# ProPrj_USB_Hub_Port_PCB_2026-06-07.net
KiCad netlist of a schematic drawn in EasyEDA Pro
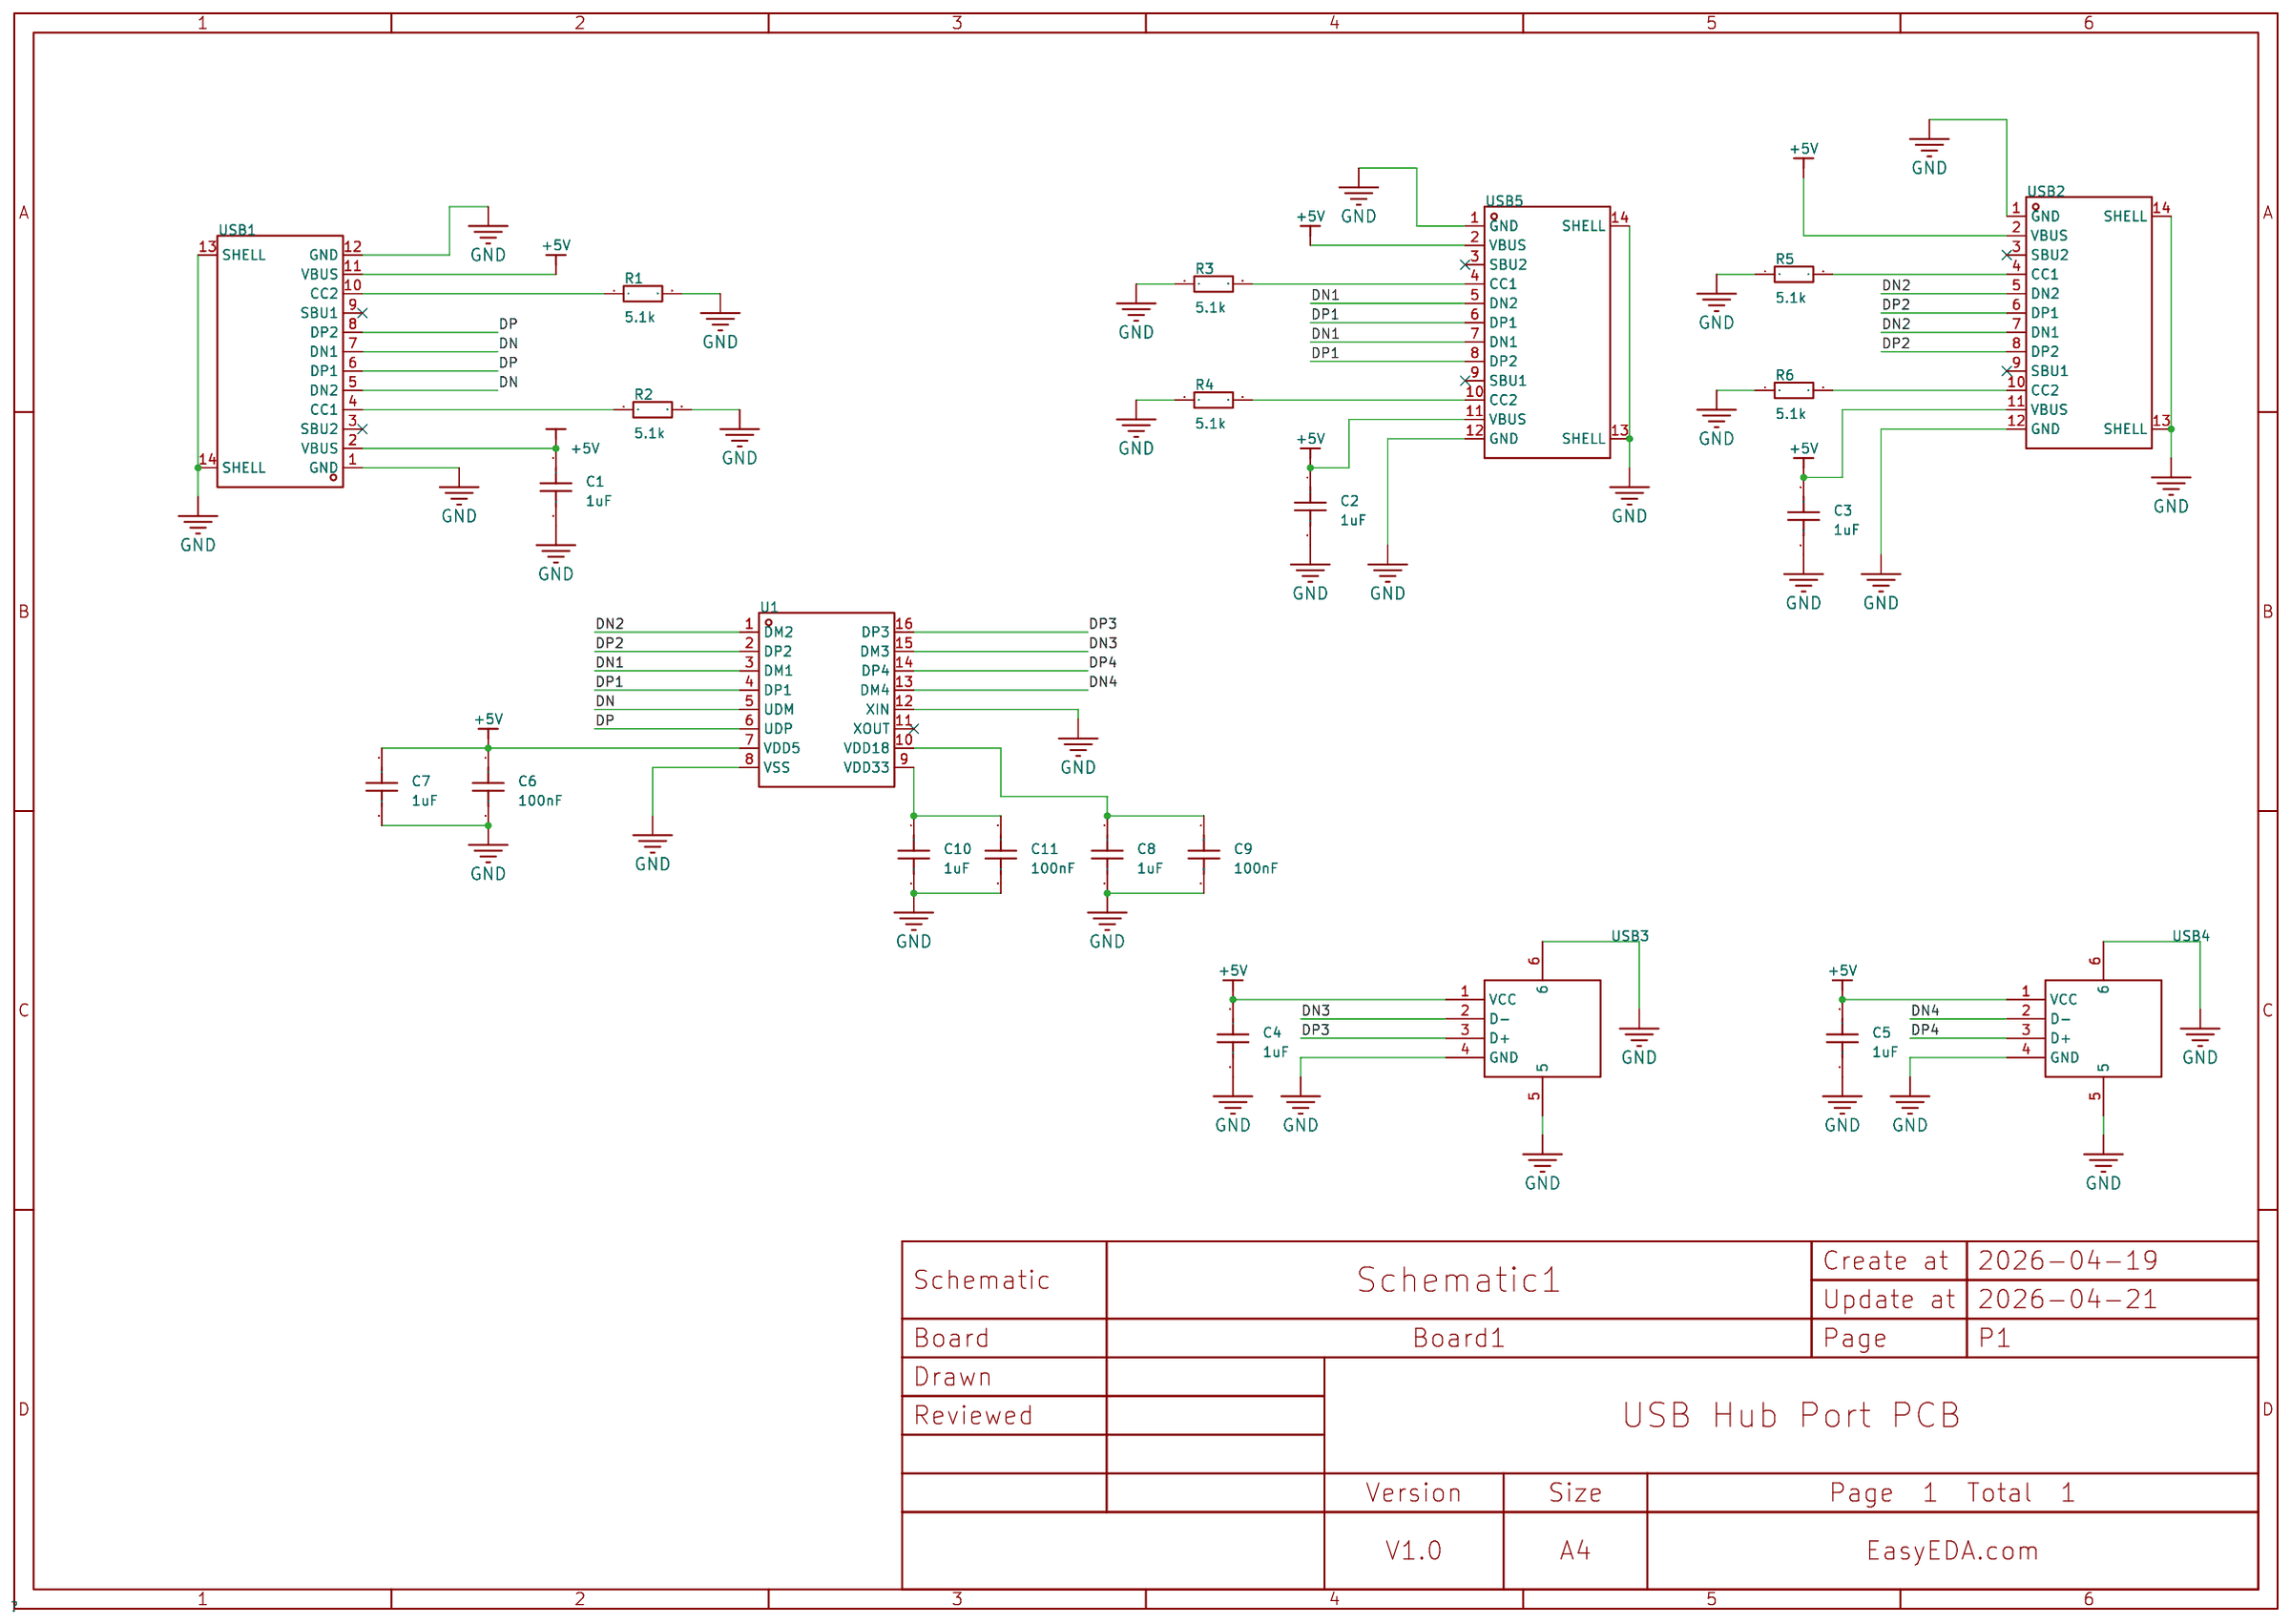
[diagram p0: schematic sheet]

(export (version "E")
  (design (tool "Eeschema 10.0.6"))
  (components
    (comp (ref "C1") (value "1uF") (footprint "easyedapro:C0603") (libsource (lib "easyedapro") (part "CAP")))
    (comp (ref "C2") (value "1uF") (footprint "easyedapro:C0603") (libsource (lib "easyedapro") (part "CAP")))
    (comp (ref "C3") (value "1uF") (footprint "easyedapro:C0603") (libsource (lib "easyedapro") (part "CAP")))
    (comp (ref "C4") (value "1uF") (footprint "easyedapro:C0603") (libsource (lib "easyedapro") (part "CAP")))
    (comp (ref "C5") (value "1uF") (footprint "easyedapro:C0603") (libsource (lib "easyedapro") (part "CAP")))
    (comp (ref "C6")
      (value "100nF")
      (footprint "easyedapro:C0603")
      (libsource (lib "easyedapro") (part "CAP"))
    )
    (comp (ref "C7") (value "1uF") (footprint "easyedapro:C0603") (libsource (lib "easyedapro") (part "CAP")))
    (comp (ref "C8") (value "1uF") (footprint "easyedapro:C0603") (libsource (lib "easyedapro") (part "CAP")))
    (comp (ref "C9")
      (value "100nF")
      (footprint "easyedapro:C0603")
      (libsource (lib "easyedapro") (part "CAP"))
    )
    (comp (ref "C10")
      (value "1uF")
      (footprint "easyedapro:C0603")
      (libsource (lib "easyedapro") (part "CAP"))
    )
    (comp (ref "C11")
      (value "100nF")
      (footprint "easyedapro:C0603")
      (libsource (lib "easyedapro") (part "CAP"))
    )
    (comp (ref "R1")
      (value "5.1k")
      (footprint "easyedapro:R0603")
      (libsource (lib "easyedapro") (part "Res"))
    )
    (comp (ref "R2")
      (value "5.1k")
      (footprint "easyedapro:R0603")
      (libsource (lib "easyedapro") (part "Res"))
    )
    (comp (ref "R3")
      (value "5.1k")
      (footprint "easyedapro:R0603")
      (libsource (lib "easyedapro") (part "Res"))
    )
    (comp (ref "R4")
      (value "5.1k")
      (footprint "easyedapro:R0603")
      (libsource (lib "easyedapro") (part "Res"))
    )
    (comp (ref "R5")
      (value "5.1k")
      (footprint "easyedapro:R0603")
      (libsource (lib "easyedapro") (part "Res"))
    )
    (comp (ref "R6")
      (value "5.1k")
      (footprint "easyedapro:R0603")
      (libsource (lib "easyedapro") (part "Res"))
    )
    (comp (ref "U1")
      (value "SL2.1s")
      (footprint "easyedapro:SSOP-16_L4.6-W2.6-P0.53-LS4.0-BL")
      (fields (field (name "Manufacturer") "CoreChips(和芯润德)"))
      (libsource (lib "easyedapro") (part "SL2.1S"))
    )
    (comp (ref "USB1")
      (value "TYPE-C 16PIN 2MD(073)")
      (footprint "easyedapro:USB-C-SMD_TYPE-C-6PIN-2MD-073")
      (fields (field (name "Manufacturer") "SHOU HAN(首韩)"))
      (libsource (lib "easyedapro") (part "TYPE-C 16PIN 2MD(073)"))
    )
    (comp (ref "USB2")
      (value "TYPE-C 16PIN 2MD(073)")
      (footprint "easyedapro:USB-C-SMD_TYPE-C-6PIN-2MD-073")
      (fields (field (name "Manufacturer") "SHOU HAN(首韩)"))
      (libsource (lib "easyedapro") (part "TYPE-C 16PIN 2MD(073)"))
    )
    (comp (ref "USB3")
      (value "10.0 QHHTZB6.3")
      (footprint "easyedapro:USB-A-TH_10.0QHHTZB6.3")
      (fields (field (name "Manufacturer") "SHOU HAN(首韩)"))
      (libsource (lib "easyedapro") (part "10.0 QHHTZB6.3"))
    )
    (comp (ref "USB4")
      (value "10.0 QHHTZB6.3")
      (footprint "easyedapro:USB-A-TH_10.0QHHTZB6.3")
      (fields (field (name "Manufacturer") "SHOU HAN(首韩)"))
      (libsource (lib "easyedapro") (part "10.0 QHHTZB6.3"))
    )
    (comp (ref "USB5")
      (value "TYPE-C 16PIN 2MD(073)")
      (footprint "easyedapro:USB-C-SMD_TYPE-C-6PIN-2MD-073")
      (fields (field (name "Manufacturer") "SHOU HAN(首韩)"))
      (libsource (lib "easyedapro") (part "TYPE-C 16PIN 2MD(073)"))
    )
  )
  (nets
    (net (code "1") (name "+5V") (class "Default")
      (node (ref "C1") (pin "1") (pinfunction "1_1") (pintype "input"))
      (node (ref "C2") (pin "1") (pinfunction "1_1") (pintype "input"))
      (node (ref "C3") (pin "1") (pinfunction "1_1") (pintype "input"))
      (node (ref "C4") (pin "1") (pinfunction "1_1") (pintype "input"))
      (node (ref "C5") (pin "1") (pinfunction "1_1") (pintype "input"))
      (node (ref "C6") (pin "1") (pinfunction "1_1") (pintype "input"))
      (node (ref "C7") (pin "1") (pinfunction "1_1") (pintype "input"))
      (node (ref "U1") (pin "7") (pinfunction "VDD5_7") (pintype "unspecified"))
      (node (ref "USB1") (pin "11") (pinfunction "VBUS_11") (pintype "unspecified"))
      (node (ref "USB1") (pin "2") (pinfunction "VBUS_2") (pintype "unspecified"))
      (node (ref "USB2") (pin "11") (pinfunction "VBUS_11") (pintype "unspecified"))
      (node (ref "USB2") (pin "2") (pinfunction "VBUS_2") (pintype "unspecified"))
      (node (ref "USB3") (pin "1") (pinfunction "VCC_1") (pintype "unspecified"))
      (node (ref "USB4") (pin "1") (pinfunction "VCC_1") (pintype "unspecified"))
      (node (ref "USB5") (pin "11") (pinfunction "VBUS_11") (pintype "unspecified"))
      (node (ref "USB5") (pin "2") (pinfunction "VBUS_2") (pintype "unspecified"))
    )
    (net (code "2") (name "/DN") (class "Default")
      (node (ref "U1") (pin "5") (pinfunction "UDM_5") (pintype "unspecified"))
      (node (ref "USB1") (pin "5") (pinfunction "DN2_5") (pintype "unspecified"))
      (node (ref "USB1") (pin "7") (pinfunction "DN1_7") (pintype "unspecified"))
    )
    (net (code "3") (name "/DN1") (class "Default")
      (node (ref "U1") (pin "3") (pinfunction "DM1_3") (pintype "unspecified"))
      (node (ref "USB5") (pin "5") (pinfunction "DN2_5") (pintype "unspecified"))
      (node (ref "USB5") (pin "7") (pinfunction "DN1_7") (pintype "unspecified"))
    )
    (net (code "4") (name "/DN2") (class "Default")
      (node (ref "U1") (pin "1") (pinfunction "DM2_1") (pintype "unspecified"))
      (node (ref "USB2") (pin "5") (pinfunction "DN2_5") (pintype "unspecified"))
      (node (ref "USB2") (pin "7") (pinfunction "DN1_7") (pintype "unspecified"))
    )
    (net (code "5") (name "/DN3") (class "Default")
      (node (ref "U1") (pin "15") (pinfunction "DM3_15") (pintype "unspecified"))
      (node (ref "USB3") (pin "2") (pinfunction "D-_2") (pintype "unspecified"))
    )
    (net (code "6") (name "/DN4") (class "Default")
      (node (ref "U1") (pin "13") (pinfunction "DM4_13") (pintype "unspecified"))
      (node (ref "USB4") (pin "2") (pinfunction "D-_2") (pintype "unspecified"))
    )
    (net (code "7") (name "/DP") (class "Default")
      (node (ref "U1") (pin "6") (pinfunction "UDP_6") (pintype "unspecified"))
      (node (ref "USB1") (pin "6") (pinfunction "DP1_6") (pintype "unspecified"))
      (node (ref "USB1") (pin "8") (pinfunction "DP2_8") (pintype "unspecified"))
    )
    (net (code "8") (name "/DP1") (class "Default")
      (node (ref "U1") (pin "4") (pinfunction "DP1_4") (pintype "unspecified"))
      (node (ref "USB5") (pin "6") (pinfunction "DP1_6") (pintype "unspecified"))
      (node (ref "USB5") (pin "8") (pinfunction "DP2_8") (pintype "unspecified"))
    )
    (net (code "9") (name "/DP2") (class "Default")
      (node (ref "U1") (pin "2") (pinfunction "DP2_2") (pintype "unspecified"))
      (node (ref "USB2") (pin "6") (pinfunction "DP1_6") (pintype "unspecified"))
      (node (ref "USB2") (pin "8") (pinfunction "DP2_8") (pintype "unspecified"))
    )
    (net (code "10") (name "/DP3") (class "Default")
      (node (ref "U1") (pin "16") (pinfunction "DP3_16") (pintype "unspecified"))
      (node (ref "USB3") (pin "3") (pinfunction "D+_3") (pintype "unspecified"))
    )
    (net (code "11") (name "/DP4") (class "Default")
      (node (ref "U1") (pin "14") (pinfunction "DP4_14") (pintype "unspecified"))
      (node (ref "USB4") (pin "3") (pinfunction "D+_3") (pintype "unspecified"))
    )
    (net (code "12") (name "GND") (class "Default")
      (node (ref "C1") (pin "2") (pinfunction "2_2") (pintype "input"))
      (node (ref "C10") (pin "2") (pinfunction "2_2") (pintype "input"))
      (node (ref "C11") (pin "2") (pinfunction "2_2") (pintype "input"))
      (node (ref "C2") (pin "2") (pinfunction "2_2") (pintype "input"))
      (node (ref "C3") (pin "2") (pinfunction "2_2") (pintype "input"))
      (node (ref "C4") (pin "2") (pinfunction "2_2") (pintype "input"))
      (node (ref "C5") (pin "2") (pinfunction "2_2") (pintype "input"))
      (node (ref "C6") (pin "2") (pinfunction "2_2") (pintype "input"))
      (node (ref "C7") (pin "2") (pinfunction "2_2") (pintype "input"))
      (node (ref "C8") (pin "2") (pinfunction "2_2") (pintype "input"))
      (node (ref "C9") (pin "2") (pinfunction "2_2") (pintype "input"))
      (node (ref "R1") (pin "2") (pinfunction "2_2") (pintype "input"))
      (node (ref "R2") (pin "2") (pinfunction "2_2") (pintype "input"))
      (node (ref "R3") (pin "1") (pinfunction "1_1") (pintype "input"))
      (node (ref "R4") (pin "1") (pinfunction "1_1") (pintype "input"))
      (node (ref "R5") (pin "1") (pinfunction "1_1") (pintype "input"))
      (node (ref "R6") (pin "1") (pinfunction "1_1") (pintype "input"))
      (node (ref "U1") (pin "12") (pinfunction "XIN_12") (pintype "unspecified"))
      (node (ref "U1") (pin "8") (pinfunction "VSS_8") (pintype "unspecified"))
      (node (ref "USB1") (pin "1") (pinfunction "GND_1") (pintype "unspecified"))
      (node (ref "USB1") (pin "12") (pinfunction "GND_12") (pintype "unspecified"))
      (node (ref "USB1") (pin "13") (pinfunction "SHELL_13") (pintype "unspecified"))
      (node (ref "USB1") (pin "14") (pinfunction "SHELL_14") (pintype "unspecified"))
      (node (ref "USB2") (pin "1") (pinfunction "GND_1") (pintype "unspecified"))
      (node (ref "USB2") (pin "12") (pinfunction "GND_12") (pintype "unspecified"))
      (node (ref "USB2") (pin "13") (pinfunction "SHELL_13") (pintype "unspecified"))
      (node (ref "USB2") (pin "14") (pinfunction "SHELL_14") (pintype "unspecified"))
      (node (ref "USB3") (pin "4") (pinfunction "GND_4") (pintype "unspecified"))
      (node (ref "USB3") (pin "5") (pinfunction "5_5") (pintype "unspecified"))
      (node (ref "USB3") (pin "6") (pinfunction "6_6") (pintype "unspecified"))
      (node (ref "USB4") (pin "4") (pinfunction "GND_4") (pintype "unspecified"))
      (node (ref "USB4") (pin "5") (pinfunction "5_5") (pintype "unspecified"))
      (node (ref "USB4") (pin "6") (pinfunction "6_6") (pintype "unspecified"))
      (node (ref "USB5") (pin "1") (pinfunction "GND_1") (pintype "unspecified"))
      (node (ref "USB5") (pin "12") (pinfunction "GND_12") (pintype "unspecified"))
      (node (ref "USB5") (pin "13") (pinfunction "SHELL_13") (pintype "unspecified"))
      (node (ref "USB5") (pin "14") (pinfunction "SHELL_14") (pintype "unspecified"))
    )
    (net (code "13") (name "Net-(U1-VDD18)") (class "Default")
      (node (ref "C8") (pin "1") (pinfunction "1_1") (pintype "input"))
      (node (ref "C9") (pin "1") (pinfunction "1_1") (pintype "input"))
      (node (ref "U1") (pin "10") (pinfunction "VDD18_10") (pintype "unspecified"))
    )
    (net (code "14") (name "Net-(U1-VDD33)") (class "Default")
      (node (ref "C10") (pin "1") (pinfunction "1_1") (pintype "input"))
      (node (ref "C11") (pin "1") (pinfunction "1_1") (pintype "input"))
      (node (ref "U1") (pin "9") (pinfunction "VDD33_9") (pintype "unspecified"))
    )
    (net (code "15") (name "Net-(USB1-CC1)") (class "Default")
      (node (ref "R2") (pin "1") (pinfunction "1_1") (pintype "input"))
      (node (ref "USB1") (pin "4") (pinfunction "CC1_4") (pintype "unspecified"))
    )
    (net (code "16") (name "Net-(USB1-CC2)") (class "Default")
      (node (ref "R1") (pin "1") (pinfunction "1_1") (pintype "input"))
      (node (ref "USB1") (pin "10") (pinfunction "CC2_10") (pintype "unspecified"))
    )
    (net (code "17") (name "Net-(USB2-CC1)") (class "Default")
      (node (ref "R5") (pin "2") (pinfunction "2_2") (pintype "input"))
      (node (ref "USB2") (pin "4") (pinfunction "CC1_4") (pintype "unspecified"))
    )
    (net (code "18") (name "Net-(USB2-CC2)") (class "Default")
      (node (ref "R6") (pin "2") (pinfunction "2_2") (pintype "input"))
      (node (ref "USB2") (pin "10") (pinfunction "CC2_10") (pintype "unspecified"))
    )
    (net (code "19") (name "Net-(USB5-CC1)") (class "Default")
      (node (ref "R3") (pin "2") (pinfunction "2_2") (pintype "input"))
      (node (ref "USB5") (pin "4") (pinfunction "CC1_4") (pintype "unspecified"))
    )
    (net (code "20") (name "Net-(USB5-CC2)") (class "Default")
      (node (ref "R4") (pin "2") (pinfunction "2_2") (pintype "input"))
      (node (ref "USB5") (pin "10") (pinfunction "CC2_10") (pintype "unspecified"))
    )
    (net (code "21") (name "unconnected-(U1-XOUT-Pad11)") (class "Default")
      (node (ref "U1") (pin "11") (pinfunction "XOUT_11") (pintype "unspecified+no_connect"))
    )
    (net (code "22") (name "unconnected-(USB1-SBU1-Pad9)") (class "Default")
      (node (ref "USB1") (pin "9") (pinfunction "SBU1_9") (pintype "unspecified+no_connect"))
    )
    (net (code "23") (name "unconnected-(USB1-SBU2-Pad3)") (class "Default")
      (node (ref "USB1") (pin "3") (pinfunction "SBU2_3") (pintype "unspecified+no_connect"))
    )
    (net (code "24") (name "unconnected-(USB2-SBU1-Pad9)") (class "Default")
      (node (ref "USB2") (pin "9") (pinfunction "SBU1_9") (pintype "unspecified+no_connect"))
    )
    (net (code "25") (name "unconnected-(USB2-SBU2-Pad3)") (class "Default")
      (node (ref "USB2") (pin "3") (pinfunction "SBU2_3") (pintype "unspecified+no_connect"))
    )
    (net (code "26") (name "unconnected-(USB5-SBU1-Pad9)") (class "Default")
      (node (ref "USB5") (pin "9") (pinfunction "SBU1_9") (pintype "unspecified+no_connect"))
    )
    (net (code "27") (name "unconnected-(USB5-SBU2-Pad3)") (class "Default")
      (node (ref "USB5") (pin "3") (pinfunction "SBU2_3") (pintype "unspecified+no_connect"))
    )
  )
)
